# VLP.net
KiCad netlist of a schematic drawn in Altium Designer
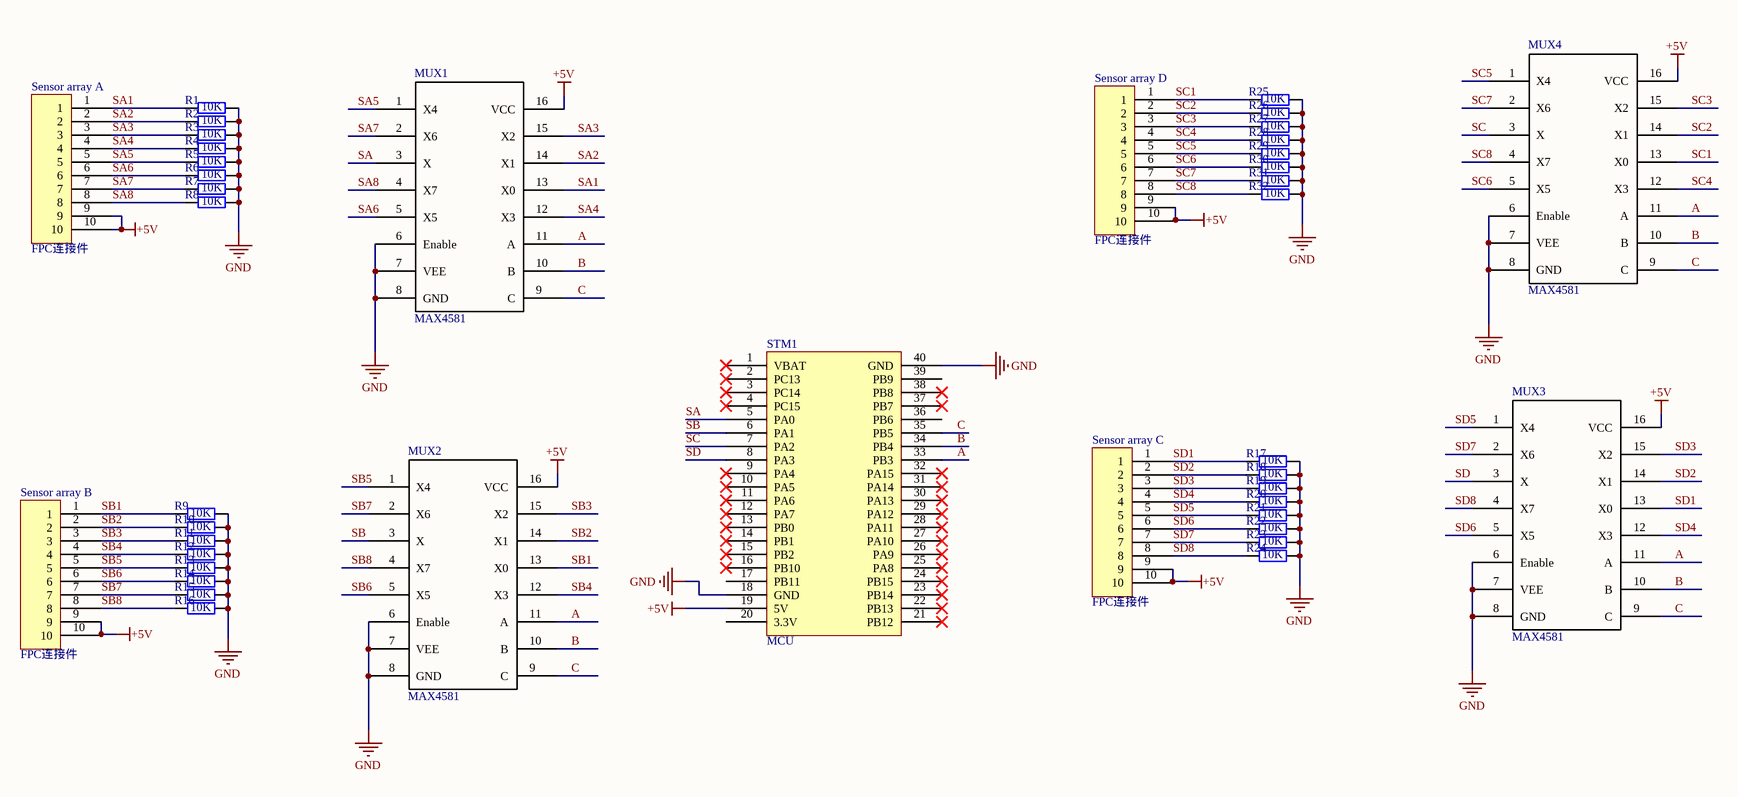
[diagram p0: VLP.SchDoc]

(export (version "E")
  (design (tool "Eeschema 10.0.6"))
  (components
    (comp (ref "MUX1") (value "MAX4581") (footprint "MAX4581") (libsource (lib "VLP") (part "MAX4581")))
    (comp (ref "MUX2") (value "MAX4581") (footprint "MAX4581") (libsource (lib "VLP") (part "MAX4581")))
    (comp (ref "MUX3") (value "MAX4581") (footprint "MAX4581") (libsource (lib "VLP") (part "MAX4581")))
    (comp (ref "MUX4") (value "MAX4581") (footprint "MAX4581") (libsource (lib "VLP") (part "MAX4581")))
    (comp (ref "R1")
      (value "10K")
      (footprint "0603c")
      (description "Resistor")
      (fields (field (name "Comment") "Res2") (field (name "PUBLISHER") "Altium Limited"))
      (libsource (lib "Miscellaneous Devices") (part "Res2"))
    )
    (comp (ref "R2")
      (value "10K")
      (footprint "0603c")
      (description "Resistor")
      (fields (field (name "Comment") "Res2") (field (name "PUBLISHER") "Altium Limited"))
      (libsource (lib "Miscellaneous Devices") (part "Res2"))
    )
    (comp (ref "R3")
      (value "10K")
      (footprint "0603c")
      (description "Resistor")
      (fields (field (name "Comment") "Res2") (field (name "PUBLISHER") "Altium Limited"))
      (libsource (lib "Miscellaneous Devices") (part "Res2"))
    )
    (comp (ref "R4")
      (value "10K")
      (footprint "0603c")
      (description "Resistor")
      (fields (field (name "Comment") "Res2") (field (name "PUBLISHER") "Altium Limited"))
      (libsource (lib "Miscellaneous Devices") (part "Res2"))
    )
    (comp (ref "R5")
      (value "10K")
      (footprint "0603c")
      (description "Resistor")
      (fields (field (name "Comment") "Res2") (field (name "PUBLISHER") "Altium Limited"))
      (libsource (lib "Miscellaneous Devices") (part "Res2"))
    )
    (comp (ref "R6")
      (value "10K")
      (footprint "0603c")
      (description "Resistor")
      (fields (field (name "Comment") "Res2") (field (name "PUBLISHER") "Altium Limited"))
      (libsource (lib "Miscellaneous Devices") (part "Res2"))
    )
    (comp (ref "R7")
      (value "10K")
      (footprint "0603c")
      (description "Resistor")
      (fields (field (name "Comment") "Res2") (field (name "PUBLISHER") "Altium Limited"))
      (libsource (lib "Miscellaneous Devices") (part "Res2"))
    )
    (comp (ref "R8")
      (value "10K")
      (footprint "0603c")
      (description "Resistor")
      (fields (field (name "Comment") "Res2") (field (name "PUBLISHER") "Altium Limited"))
      (libsource (lib "Miscellaneous Devices") (part "Res2"))
    )
    (comp (ref "R9")
      (value "10K")
      (footprint "0603c")
      (description "Resistor")
      (fields (field (name "Comment") "Res2") (field (name "PUBLISHER") "Altium Limited"))
      (libsource (lib "Miscellaneous Devices") (part "Res2"))
    )
    (comp (ref "R10")
      (value "10K")
      (footprint "0603c")
      (description "Resistor")
      (fields (field (name "Comment") "Res2") (field (name "PUBLISHER") "Altium Limited"))
      (libsource (lib "Miscellaneous Devices") (part "Res2"))
    )
    (comp (ref "R11")
      (value "10K")
      (footprint "0603c")
      (description "Resistor")
      (fields (field (name "Comment") "Res2") (field (name "PUBLISHER") "Altium Limited"))
      (libsource (lib "Miscellaneous Devices") (part "Res2"))
    )
    (comp (ref "R12")
      (value "10K")
      (footprint "0603c")
      (description "Resistor")
      (fields (field (name "Comment") "Res2") (field (name "PUBLISHER") "Altium Limited"))
      (libsource (lib "Miscellaneous Devices") (part "Res2"))
    )
    (comp (ref "R13")
      (value "10K")
      (footprint "0603c")
      (description "Resistor")
      (fields (field (name "Comment") "Res2") (field (name "PUBLISHER") "Altium Limited"))
      (libsource (lib "Miscellaneous Devices") (part "Res2"))
    )
    (comp (ref "R14")
      (value "10K")
      (footprint "0603c")
      (description "Resistor")
      (fields (field (name "Comment") "Res2") (field (name "PUBLISHER") "Altium Limited"))
      (libsource (lib "Miscellaneous Devices") (part "Res2"))
    )
    (comp (ref "R15")
      (value "10K")
      (footprint "0603c")
      (description "Resistor")
      (fields (field (name "Comment") "Res2") (field (name "PUBLISHER") "Altium Limited"))
      (libsource (lib "Miscellaneous Devices") (part "Res2"))
    )
    (comp (ref "R16")
      (value "10K")
      (footprint "0603c")
      (description "Resistor")
      (fields (field (name "Comment") "Res2") (field (name "PUBLISHER") "Altium Limited"))
      (libsource (lib "Miscellaneous Devices") (part "Res2"))
    )
    (comp (ref "R17")
      (value "10K")
      (footprint "0603c")
      (description "Resistor")
      (fields (field (name "Comment") "Res2") (field (name "PUBLISHER") "Altium Limited"))
      (libsource (lib "Miscellaneous Devices") (part "Res2"))
    )
    (comp (ref "R18")
      (value "10K")
      (footprint "0603c")
      (description "Resistor")
      (fields (field (name "Comment") "Res2") (field (name "PUBLISHER") "Altium Limited"))
      (libsource (lib "Miscellaneous Devices") (part "Res2"))
    )
    (comp (ref "R19")
      (value "10K")
      (footprint "0603c")
      (description "Resistor")
      (fields (field (name "Comment") "Res2") (field (name "PUBLISHER") "Altium Limited"))
      (libsource (lib "Miscellaneous Devices") (part "Res2"))
    )
    (comp (ref "R20")
      (value "10K")
      (footprint "0603c")
      (description "Resistor")
      (fields (field (name "Comment") "Res2") (field (name "PUBLISHER") "Altium Limited"))
      (libsource (lib "Miscellaneous Devices") (part "Res2"))
    )
    (comp (ref "R21")
      (value "10K")
      (footprint "0603c")
      (description "Resistor")
      (fields (field (name "Comment") "Res2") (field (name "PUBLISHER") "Altium Limited"))
      (libsource (lib "Miscellaneous Devices") (part "Res2"))
    )
    (comp (ref "R22")
      (value "10K")
      (footprint "0603c")
      (description "Resistor")
      (fields (field (name "Comment") "Res2") (field (name "PUBLISHER") "Altium Limited"))
      (libsource (lib "Miscellaneous Devices") (part "Res2"))
    )
    (comp (ref "R23")
      (value "10K")
      (footprint "0603c")
      (description "Resistor")
      (fields (field (name "Comment") "Res2") (field (name "PUBLISHER") "Altium Limited"))
      (libsource (lib "Miscellaneous Devices") (part "Res2"))
    )
    (comp (ref "R24")
      (value "10K")
      (footprint "0603c")
      (description "Resistor")
      (fields (field (name "Comment") "Res2") (field (name "PUBLISHER") "Altium Limited"))
      (libsource (lib "Miscellaneous Devices") (part "Res2"))
    )
    (comp (ref "R25")
      (value "10K")
      (footprint "0603c")
      (description "Resistor")
      (fields (field (name "Comment") "Res2") (field (name "PUBLISHER") "Altium Limited"))
      (libsource (lib "Miscellaneous Devices") (part "Res2"))
    )
    (comp (ref "R26")
      (value "10K")
      (footprint "0603c")
      (description "Resistor")
      (fields (field (name "Comment") "Res2") (field (name "PUBLISHER") "Altium Limited"))
      (libsource (lib "Miscellaneous Devices") (part "Res2"))
    )
    (comp (ref "R27")
      (value "10K")
      (footprint "0603c")
      (description "Resistor")
      (fields (field (name "Comment") "Res2") (field (name "PUBLISHER") "Altium Limited"))
      (libsource (lib "Miscellaneous Devices") (part "Res2"))
    )
    (comp (ref "R28")
      (value "10K")
      (footprint "0603c")
      (description "Resistor")
      (fields (field (name "Comment") "Res2") (field (name "PUBLISHER") "Altium Limited"))
      (libsource (lib "Miscellaneous Devices") (part "Res2"))
    )
    (comp (ref "R29")
      (value "10K")
      (footprint "0603c")
      (description "Resistor")
      (fields (field (name "Comment") "Res2") (field (name "PUBLISHER") "Altium Limited"))
      (libsource (lib "Miscellaneous Devices") (part "Res2"))
    )
    (comp (ref "R30")
      (value "10K")
      (footprint "0603c")
      (description "Resistor")
      (fields (field (name "Comment") "Res2") (field (name "PUBLISHER") "Altium Limited"))
      (libsource (lib "Miscellaneous Devices") (part "Res2"))
    )
    (comp (ref "R31")
      (value "10K")
      (footprint "0603c")
      (description "Resistor")
      (fields (field (name "Comment") "Res2") (field (name "PUBLISHER") "Altium Limited"))
      (libsource (lib "Miscellaneous Devices") (part "Res2"))
    )
    (comp (ref "R32")
      (value "10K")
      (footprint "0603c")
      (description "Resistor")
      (fields (field (name "Comment") "Res2") (field (name "PUBLISHER") "Altium Limited"))
      (libsource (lib "Miscellaneous Devices") (part "Res2"))
    )
    (comp (ref "Sensor array A")
      (value "FPC连接件")
      (footprint "FPC连接器-10P")
      (libsource (lib "altium-import") (part "root_0_FPC连接件_"))
    )
    (comp (ref "Sensor array B")
      (value "FPC连接件")
      (footprint "FPC连接器-10P")
      (libsource (lib "altium-import") (part "root_0_FPC连接件_"))
    )
    (comp (ref "Sensor array C")
      (value "FPC连接件")
      (footprint "FPC连接器-10P")
      (libsource (lib "altium-import") (part "root_0_FPC连接件_"))
    )
    (comp (ref "Sensor array D")
      (value "FPC连接件")
      (footprint "FPC连接器-10P")
      (libsource (lib "altium-import") (part "root_0_FPC连接件_"))
    )
    (comp (ref "STM1")
      (value "MCU")
      (footprint "STM32F103C8T6-4")
      (libsource (lib "STM32F103C8T6原理图库文件") (part "Component_1"))
    )
  )
  (nets
    (net (code "1") (name "+5V") (class "Default")
      (node (ref "MUX1") (pin "16") (pinfunction "VCC_16") (pintype "passive"))
      (node (ref "MUX2") (pin "16") (pinfunction "VCC_16") (pintype "passive"))
      (node (ref "MUX3") (pin "16") (pinfunction "VCC_16") (pintype "passive"))
      (node (ref "MUX4") (pin "16") (pinfunction "VCC_16") (pintype "passive"))
      (node (ref "STM1") (pin "19") (pinfunction "5V_19") (pintype "passive"))
      (node (ref "Sensor array A") (pin "10") (pinfunction "10_10") (pintype "passive"))
      (node (ref "Sensor array A") (pin "9") (pinfunction "9_9") (pintype "passive"))
      (node (ref "Sensor array B") (pin "10") (pinfunction "10_10") (pintype "passive"))
      (node (ref "Sensor array B") (pin "9") (pinfunction "9_9") (pintype "passive"))
      (node (ref "Sensor array C") (pin "10") (pinfunction "10_10") (pintype "passive"))
      (node (ref "Sensor array C") (pin "9") (pinfunction "9_9") (pintype "passive"))
      (node (ref "Sensor array D") (pin "10") (pinfunction "10_10") (pintype "passive"))
      (node (ref "Sensor array D") (pin "9") (pinfunction "9_9") (pintype "passive"))
    )
    (net (code "2") (name "/A") (class "Default")
      (node (ref "MUX1") (pin "11") (pinfunction "A_11") (pintype "passive"))
      (node (ref "MUX2") (pin "11") (pinfunction "A_11") (pintype "passive"))
      (node (ref "MUX3") (pin "11") (pinfunction "A_11") (pintype "passive"))
      (node (ref "MUX4") (pin "11") (pinfunction "A_11") (pintype "passive"))
      (node (ref "STM1") (pin "33") (pinfunction "PB3_33") (pintype "passive"))
    )
    (net (code "3") (name "/B") (class "Default")
      (node (ref "MUX1") (pin "10") (pinfunction "B_10") (pintype "passive"))
      (node (ref "MUX2") (pin "10") (pinfunction "B_10") (pintype "passive"))
      (node (ref "MUX3") (pin "10") (pinfunction "B_10") (pintype "passive"))
      (node (ref "MUX4") (pin "10") (pinfunction "B_10") (pintype "passive"))
      (node (ref "STM1") (pin "34") (pinfunction "PB4_34") (pintype "passive"))
    )
    (net (code "4") (name "/C") (class "Default")
      (node (ref "MUX1") (pin "9") (pinfunction "C_9") (pintype "passive"))
      (node (ref "MUX2") (pin "9") (pinfunction "C_9") (pintype "passive"))
      (node (ref "MUX3") (pin "9") (pinfunction "C_9") (pintype "passive"))
      (node (ref "MUX4") (pin "9") (pinfunction "C_9") (pintype "passive"))
      (node (ref "STM1") (pin "35") (pinfunction "PB5_35") (pintype "passive"))
    )
    (net (code "5") (name "/SA") (class "Default")
      (node (ref "MUX1") (pin "3") (pinfunction "X_3") (pintype "passive"))
      (node (ref "STM1") (pin "5") (pinfunction "PA0_5") (pintype "passive"))
    )
    (net (code "6") (name "/SA1") (class "Default")
      (node (ref "MUX1") (pin "13") (pinfunction "X0_13") (pintype "passive"))
      (node (ref "R1") (pin "1") (pinfunction "1_1") (pintype "passive"))
      (node (ref "Sensor array A") (pin "1") (pinfunction "1_1") (pintype "passive"))
    )
    (net (code "7") (name "/SA2") (class "Default")
      (node (ref "MUX1") (pin "14") (pinfunction "X1_14") (pintype "passive"))
      (node (ref "R2") (pin "1") (pinfunction "1_1") (pintype "passive"))
      (node (ref "Sensor array A") (pin "2") (pinfunction "2_2") (pintype "passive"))
    )
    (net (code "8") (name "/SA3") (class "Default")
      (node (ref "MUX1") (pin "15") (pinfunction "X2_15") (pintype "passive"))
      (node (ref "R3") (pin "1") (pinfunction "1_1") (pintype "passive"))
      (node (ref "Sensor array A") (pin "3") (pinfunction "3_3") (pintype "passive"))
    )
    (net (code "9") (name "/SA4") (class "Default")
      (node (ref "MUX1") (pin "12") (pinfunction "X3_12") (pintype "passive"))
      (node (ref "R4") (pin "1") (pinfunction "1_1") (pintype "passive"))
      (node (ref "Sensor array A") (pin "4") (pinfunction "4_4") (pintype "passive"))
    )
    (net (code "10") (name "/SA5") (class "Default")
      (node (ref "MUX1") (pin "1") (pinfunction "X4_1") (pintype "passive"))
      (node (ref "R5") (pin "1") (pinfunction "1_1") (pintype "passive"))
      (node (ref "Sensor array A") (pin "5") (pinfunction "5_5") (pintype "passive"))
    )
    (net (code "11") (name "/SA6") (class "Default")
      (node (ref "MUX1") (pin "5") (pinfunction "X5_5") (pintype "passive"))
      (node (ref "R6") (pin "1") (pinfunction "1_1") (pintype "passive"))
      (node (ref "Sensor array A") (pin "6") (pinfunction "6_6") (pintype "passive"))
    )
    (net (code "12") (name "/SA7") (class "Default")
      (node (ref "MUX1") (pin "2") (pinfunction "X6_2") (pintype "passive"))
      (node (ref "R7") (pin "1") (pinfunction "1_1") (pintype "passive"))
      (node (ref "Sensor array A") (pin "7") (pinfunction "7_7") (pintype "passive"))
    )
    (net (code "13") (name "/SA8") (class "Default")
      (node (ref "MUX1") (pin "4") (pinfunction "X7_4") (pintype "passive"))
      (node (ref "R8") (pin "1") (pinfunction "1_1") (pintype "passive"))
      (node (ref "Sensor array A") (pin "8") (pinfunction "8_8") (pintype "passive"))
    )
    (net (code "14") (name "/SB") (class "Default")
      (node (ref "MUX2") (pin "3") (pinfunction "X_3") (pintype "passive"))
      (node (ref "STM1") (pin "6") (pinfunction "PA1_6") (pintype "passive"))
    )
    (net (code "15") (name "/SB1") (class "Default")
      (node (ref "MUX2") (pin "13") (pinfunction "X0_13") (pintype "passive"))
      (node (ref "R9") (pin "1") (pinfunction "1_1") (pintype "passive"))
      (node (ref "Sensor array B") (pin "1") (pinfunction "1_1") (pintype "passive"))
    )
    (net (code "16") (name "/SB2") (class "Default")
      (node (ref "MUX2") (pin "14") (pinfunction "X1_14") (pintype "passive"))
      (node (ref "R10") (pin "1") (pinfunction "1_1") (pintype "passive"))
      (node (ref "Sensor array B") (pin "2") (pinfunction "2_2") (pintype "passive"))
    )
    (net (code "17") (name "/SB3") (class "Default")
      (node (ref "MUX2") (pin "15") (pinfunction "X2_15") (pintype "passive"))
      (node (ref "R11") (pin "1") (pinfunction "1_1") (pintype "passive"))
      (node (ref "Sensor array B") (pin "3") (pinfunction "3_3") (pintype "passive"))
    )
    (net (code "18") (name "/SB4") (class "Default")
      (node (ref "MUX2") (pin "12") (pinfunction "X3_12") (pintype "passive"))
      (node (ref "R12") (pin "1") (pinfunction "1_1") (pintype "passive"))
      (node (ref "Sensor array B") (pin "4") (pinfunction "4_4") (pintype "passive"))
    )
    (net (code "19") (name "/SB5") (class "Default")
      (node (ref "MUX2") (pin "1") (pinfunction "X4_1") (pintype "passive"))
      (node (ref "R13") (pin "1") (pinfunction "1_1") (pintype "passive"))
      (node (ref "Sensor array B") (pin "5") (pinfunction "5_5") (pintype "passive"))
    )
    (net (code "20") (name "/SB6") (class "Default")
      (node (ref "MUX2") (pin "5") (pinfunction "X5_5") (pintype "passive"))
      (node (ref "R14") (pin "1") (pinfunction "1_1") (pintype "passive"))
      (node (ref "Sensor array B") (pin "6") (pinfunction "6_6") (pintype "passive"))
    )
    (net (code "21") (name "/SB7") (class "Default")
      (node (ref "MUX2") (pin "2") (pinfunction "X6_2") (pintype "passive"))
      (node (ref "R15") (pin "1") (pinfunction "1_1") (pintype "passive"))
      (node (ref "Sensor array B") (pin "7") (pinfunction "7_7") (pintype "passive"))
    )
    (net (code "22") (name "/SB8") (class "Default")
      (node (ref "MUX2") (pin "4") (pinfunction "X7_4") (pintype "passive"))
      (node (ref "R16") (pin "1") (pinfunction "1_1") (pintype "passive"))
      (node (ref "Sensor array B") (pin "8") (pinfunction "8_8") (pintype "passive"))
    )
    (net (code "23") (name "/SC") (class "Default")
      (node (ref "MUX4") (pin "3") (pinfunction "X_3") (pintype "passive"))
      (node (ref "STM1") (pin "7") (pinfunction "PA2_7") (pintype "passive"))
    )
    (net (code "24") (name "/SC1") (class "Default")
      (node (ref "MUX4") (pin "13") (pinfunction "X0_13") (pintype "passive"))
      (node (ref "R25") (pin "1") (pinfunction "1_1") (pintype "passive"))
      (node (ref "Sensor array D") (pin "1") (pinfunction "1_1") (pintype "passive"))
    )
    (net (code "25") (name "/SC2") (class "Default")
      (node (ref "MUX4") (pin "14") (pinfunction "X1_14") (pintype "passive"))
      (node (ref "R26") (pin "1") (pinfunction "1_1") (pintype "passive"))
      (node (ref "Sensor array D") (pin "2") (pinfunction "2_2") (pintype "passive"))
    )
    (net (code "26") (name "/SC3") (class "Default")
      (node (ref "MUX4") (pin "15") (pinfunction "X2_15") (pintype "passive"))
      (node (ref "R27") (pin "1") (pinfunction "1_1") (pintype "passive"))
      (node (ref "Sensor array D") (pin "3") (pinfunction "3_3") (pintype "passive"))
    )
    (net (code "27") (name "/SC4") (class "Default")
      (node (ref "MUX4") (pin "12") (pinfunction "X3_12") (pintype "passive"))
      (node (ref "R28") (pin "1") (pinfunction "1_1") (pintype "passive"))
      (node (ref "Sensor array D") (pin "4") (pinfunction "4_4") (pintype "passive"))
    )
    (net (code "28") (name "/SC5") (class "Default")
      (node (ref "MUX4") (pin "1") (pinfunction "X4_1") (pintype "passive"))
      (node (ref "R29") (pin "1") (pinfunction "1_1") (pintype "passive"))
      (node (ref "Sensor array D") (pin "5") (pinfunction "5_5") (pintype "passive"))
    )
    (net (code "29") (name "/SC6") (class "Default")
      (node (ref "MUX4") (pin "5") (pinfunction "X5_5") (pintype "passive"))
      (node (ref "R30") (pin "1") (pinfunction "1_1") (pintype "passive"))
      (node (ref "Sensor array D") (pin "6") (pinfunction "6_6") (pintype "passive"))
    )
    (net (code "30") (name "/SC7") (class "Default")
      (node (ref "MUX4") (pin "2") (pinfunction "X6_2") (pintype "passive"))
      (node (ref "R31") (pin "1") (pinfunction "1_1") (pintype "passive"))
      (node (ref "Sensor array D") (pin "7") (pinfunction "7_7") (pintype "passive"))
    )
    (net (code "31") (name "/SC8") (class "Default")
      (node (ref "MUX4") (pin "4") (pinfunction "X7_4") (pintype "passive"))
      (node (ref "R32") (pin "1") (pinfunction "1_1") (pintype "passive"))
      (node (ref "Sensor array D") (pin "8") (pinfunction "8_8") (pintype "passive"))
    )
    (net (code "32") (name "/SD") (class "Default")
      (node (ref "MUX3") (pin "3") (pinfunction "X_3") (pintype "passive"))
      (node (ref "STM1") (pin "8") (pinfunction "PA3_8") (pintype "passive"))
    )
    (net (code "33") (name "/SD1") (class "Default")
      (node (ref "MUX3") (pin "13") (pinfunction "X0_13") (pintype "passive"))
      (node (ref "R17") (pin "1") (pinfunction "1_1") (pintype "passive"))
      (node (ref "Sensor array C") (pin "1") (pinfunction "1_1") (pintype "passive"))
    )
    (net (code "34") (name "/SD2") (class "Default")
      (node (ref "MUX3") (pin "14") (pinfunction "X1_14") (pintype "passive"))
      (node (ref "R18") (pin "1") (pinfunction "1_1") (pintype "passive"))
      (node (ref "Sensor array C") (pin "2") (pinfunction "2_2") (pintype "passive"))
    )
    (net (code "35") (name "/SD3") (class "Default")
      (node (ref "MUX3") (pin "15") (pinfunction "X2_15") (pintype "passive"))
      (node (ref "R19") (pin "1") (pinfunction "1_1") (pintype "passive"))
      (node (ref "Sensor array C") (pin "3") (pinfunction "3_3") (pintype "passive"))
    )
    (net (code "36") (name "/SD4") (class "Default")
      (node (ref "MUX3") (pin "12") (pinfunction "X3_12") (pintype "passive"))
      (node (ref "R20") (pin "1") (pinfunction "1_1") (pintype "passive"))
      (node (ref "Sensor array C") (pin "4") (pinfunction "4_4") (pintype "passive"))
    )
    (net (code "37") (name "/SD5") (class "Default")
      (node (ref "MUX3") (pin "1") (pinfunction "X4_1") (pintype "passive"))
      (node (ref "R21") (pin "1") (pinfunction "1_1") (pintype "passive"))
      (node (ref "Sensor array C") (pin "5") (pinfunction "5_5") (pintype "passive"))
    )
    (net (code "38") (name "/SD6") (class "Default")
      (node (ref "MUX3") (pin "5") (pinfunction "X5_5") (pintype "passive"))
      (node (ref "R22") (pin "1") (pinfunction "1_1") (pintype "passive"))
      (node (ref "Sensor array C") (pin "6") (pinfunction "6_6") (pintype "passive"))
    )
    (net (code "39") (name "/SD7") (class "Default")
      (node (ref "MUX3") (pin "2") (pinfunction "X6_2") (pintype "passive"))
      (node (ref "R23") (pin "1") (pinfunction "1_1") (pintype "passive"))
      (node (ref "Sensor array C") (pin "7") (pinfunction "7_7") (pintype "passive"))
    )
    (net (code "40") (name "/SD8") (class "Default")
      (node (ref "MUX3") (pin "4") (pinfunction "X7_4") (pintype "passive"))
      (node (ref "R24") (pin "1") (pinfunction "1_1") (pintype "passive"))
      (node (ref "Sensor array C") (pin "8") (pinfunction "8_8") (pintype "passive"))
    )
    (net (code "41") (name "GND") (class "Default")
      (node (ref "MUX1") (pin "6") (pinfunction "Enable_6") (pintype "passive"))
      (node (ref "MUX1") (pin "7") (pinfunction "VEE_7") (pintype "passive"))
      (node (ref "MUX1") (pin "8") (pinfunction "GND_8") (pintype "passive"))
      (node (ref "MUX2") (pin "6") (pinfunction "Enable_6") (pintype "passive"))
      (node (ref "MUX2") (pin "7") (pinfunction "VEE_7") (pintype "passive"))
      (node (ref "MUX2") (pin "8") (pinfunction "GND_8") (pintype "passive"))
      (node (ref "MUX3") (pin "6") (pinfunction "Enable_6") (pintype "passive"))
      (node (ref "MUX3") (pin "7") (pinfunction "VEE_7") (pintype "passive"))
      (node (ref "MUX3") (pin "8") (pinfunction "GND_8") (pintype "passive"))
      (node (ref "MUX4") (pin "6") (pinfunction "Enable_6") (pintype "passive"))
      (node (ref "MUX4") (pin "7") (pinfunction "VEE_7") (pintype "passive"))
      (node (ref "MUX4") (pin "8") (pinfunction "GND_8") (pintype "passive"))
      (node (ref "R1") (pin "2") (pinfunction "2_2") (pintype "passive"))
      (node (ref "R10") (pin "2") (pinfunction "2_2") (pintype "passive"))
      (node (ref "R11") (pin "2") (pinfunction "2_2") (pintype "passive"))
      (node (ref "R12") (pin "2") (pinfunction "2_2") (pintype "passive"))
      (node (ref "R13") (pin "2") (pinfunction "2_2") (pintype "passive"))
      (node (ref "R14") (pin "2") (pinfunction "2_2") (pintype "passive"))
      (node (ref "R15") (pin "2") (pinfunction "2_2") (pintype "passive"))
      (node (ref "R16") (pin "2") (pinfunction "2_2") (pintype "passive"))
      (node (ref "R17") (pin "2") (pinfunction "2_2") (pintype "passive"))
      (node (ref "R18") (pin "2") (pinfunction "2_2") (pintype "passive"))
      (node (ref "R19") (pin "2") (pinfunction "2_2") (pintype "passive"))
      (node (ref "R2") (pin "2") (pinfunction "2_2") (pintype "passive"))
      (node (ref "R20") (pin "2") (pinfunction "2_2") (pintype "passive"))
      (node (ref "R21") (pin "2") (pinfunction "2_2") (pintype "passive"))
      (node (ref "R22") (pin "2") (pinfunction "2_2") (pintype "passive"))
      (node (ref "R23") (pin "2") (pinfunction "2_2") (pintype "passive"))
      (node (ref "R24") (pin "2") (pinfunction "2_2") (pintype "passive"))
      (node (ref "R25") (pin "2") (pinfunction "2_2") (pintype "passive"))
      (node (ref "R26") (pin "2") (pinfunction "2_2") (pintype "passive"))
      (node (ref "R27") (pin "2") (pinfunction "2_2") (pintype "passive"))
      (node (ref "R28") (pin "2") (pinfunction "2_2") (pintype "passive"))
      (node (ref "R29") (pin "2") (pinfunction "2_2") (pintype "passive"))
      (node (ref "R3") (pin "2") (pinfunction "2_2") (pintype "passive"))
      (node (ref "R30") (pin "2") (pinfunction "2_2") (pintype "passive"))
      (node (ref "R31") (pin "2") (pinfunction "2_2") (pintype "passive"))
      (node (ref "R32") (pin "2") (pinfunction "2_2") (pintype "passive"))
      (node (ref "R4") (pin "2") (pinfunction "2_2") (pintype "passive"))
      (node (ref "R5") (pin "2") (pinfunction "2_2") (pintype "passive"))
      (node (ref "R6") (pin "2") (pinfunction "2_2") (pintype "passive"))
      (node (ref "R7") (pin "2") (pinfunction "2_2") (pintype "passive"))
      (node (ref "R8") (pin "2") (pinfunction "2_2") (pintype "passive"))
      (node (ref "R9") (pin "2") (pinfunction "2_2") (pintype "passive"))
      (node (ref "STM1") (pin "18") (pinfunction "GND_18") (pintype "passive"))
      (node (ref "STM1") (pin "40") (pinfunction "GND_40") (pintype "passive"))
    )
    (net (code "42") (name "unconnected-(STM1-3.3V-Pad20)") (class "Default")
      (node (ref "STM1") (pin "20") (pinfunction "3.3V_20") (pintype "passive"))
    )
    (net (code "43") (name "unconnected-(STM1-PA4-Pad9)") (class "Default")
      (node (ref "STM1") (pin "9") (pinfunction "PA4_9") (pintype "passive+no_connect"))
    )
    (net (code "44") (name "unconnected-(STM1-PA5-Pad10)") (class "Default")
      (node (ref "STM1") (pin "10") (pinfunction "PA5_10") (pintype "passive+no_connect"))
    )
    (net (code "45") (name "unconnected-(STM1-PA6-Pad11)") (class "Default")
      (node (ref "STM1") (pin "11") (pinfunction "PA6_11") (pintype "passive+no_connect"))
    )
    (net (code "46") (name "unconnected-(STM1-PA7-Pad12)") (class "Default")
      (node (ref "STM1") (pin "12") (pinfunction "PA7_12") (pintype "passive+no_connect"))
    )
    (net (code "47") (name "unconnected-(STM1-PA8-Pad25)") (class "Default")
      (node (ref "STM1") (pin "25") (pinfunction "PA8_25") (pintype "passive+no_connect"))
    )
    (net (code "48") (name "unconnected-(STM1-PA9-Pad26)") (class "Default")
      (node (ref "STM1") (pin "26") (pinfunction "PA9_26") (pintype "passive+no_connect"))
    )
    (net (code "49") (name "unconnected-(STM1-PA10-Pad27)") (class "Default")
      (node (ref "STM1") (pin "27") (pinfunction "PA10_27") (pintype "passive+no_connect"))
    )
    (net (code "50") (name "unconnected-(STM1-PA11-Pad28)") (class "Default")
      (node (ref "STM1") (pin "28") (pinfunction "PA11_28") (pintype "passive+no_connect"))
    )
    (net (code "51") (name "unconnected-(STM1-PA12-Pad29)") (class "Default")
      (node (ref "STM1") (pin "29") (pinfunction "PA12_29") (pintype "passive+no_connect"))
    )
    (net (code "52") (name "unconnected-(STM1-PA13-Pad30)") (class "Default")
      (node (ref "STM1") (pin "30") (pinfunction "PA13_30") (pintype "passive+no_connect"))
    )
    (net (code "53") (name "unconnected-(STM1-PA14-Pad31)") (class "Default")
      (node (ref "STM1") (pin "31") (pinfunction "PA14_31") (pintype "passive+no_connect"))
    )
    (net (code "54") (name "unconnected-(STM1-PA15-Pad32)") (class "Default")
      (node (ref "STM1") (pin "32") (pinfunction "PA15_32") (pintype "passive+no_connect"))
    )
    (net (code "55") (name "unconnected-(STM1-PB0-Pad13)") (class "Default")
      (node (ref "STM1") (pin "13") (pinfunction "PB0_13") (pintype "passive+no_connect"))
    )
    (net (code "56") (name "unconnected-(STM1-PB1-Pad14)") (class "Default")
      (node (ref "STM1") (pin "14") (pinfunction "PB1_14") (pintype "passive+no_connect"))
    )
    (net (code "57") (name "unconnected-(STM1-PB2-Pad15)") (class "Default")
      (node (ref "STM1") (pin "15") (pinfunction "PB2_15") (pintype "passive+no_connect"))
    )
    (net (code "58") (name "unconnected-(STM1-PB6-Pad36)") (class "Default")
      (node (ref "STM1") (pin "36") (pinfunction "PB6_36") (pintype "passive"))
    )
    (net (code "59") (name "unconnected-(STM1-PB7-Pad37)") (class "Default")
      (node (ref "STM1") (pin "37") (pinfunction "PB7_37") (pintype "passive+no_connect"))
    )
    (net (code "60") (name "unconnected-(STM1-PB8-Pad38)") (class "Default")
      (node (ref "STM1") (pin "38") (pinfunction "PB8_38") (pintype "passive+no_connect"))
    )
    (net (code "61") (name "unconnected-(STM1-PB9-Pad39)") (class "Default")
      (node (ref "STM1") (pin "39") (pinfunction "PB9_39") (pintype "passive"))
    )
    (net (code "62") (name "unconnected-(STM1-PB10-Pad16)") (class "Default")
      (node (ref "STM1") (pin "16") (pinfunction "PB10_16") (pintype "passive+no_connect"))
    )
    (net (code "63") (name "unconnected-(STM1-PB11-Pad17)") (class "Default")
      (node (ref "STM1") (pin "17") (pinfunction "PB11_17") (pintype "passive"))
    )
    (net (code "64") (name "unconnected-(STM1-PB12-Pad21)") (class "Default")
      (node (ref "STM1") (pin "21") (pinfunction "PB12_21") (pintype "passive+no_connect"))
    )
    (net (code "65") (name "unconnected-(STM1-PB13-Pad22)") (class "Default")
      (node (ref "STM1") (pin "22") (pinfunction "PB13_22") (pintype "passive+no_connect"))
    )
    (net (code "66") (name "unconnected-(STM1-PB14-Pad23)") (class "Default")
      (node (ref "STM1") (pin "23") (pinfunction "PB14_23") (pintype "passive+no_connect"))
    )
    (net (code "67") (name "unconnected-(STM1-PB15-Pad24)") (class "Default")
      (node (ref "STM1") (pin "24") (pinfunction "PB15_24") (pintype "passive+no_connect"))
    )
    (net (code "68") (name "unconnected-(STM1-PC13-Pad2)") (class "Default")
      (node (ref "STM1") (pin "2") (pinfunction "PC13_2") (pintype "passive+no_connect"))
    )
    (net (code "69") (name "unconnected-(STM1-PC14-Pad3)") (class "Default")
      (node (ref "STM1") (pin "3") (pinfunction "PC14_3") (pintype "passive+no_connect"))
    )
    (net (code "70") (name "unconnected-(STM1-PC15-Pad4)") (class "Default")
      (node (ref "STM1") (pin "4") (pinfunction "PC15_4") (pintype "passive+no_connect"))
    )
    (net (code "71") (name "unconnected-(STM1-VBAT-Pad1)") (class "Default")
      (node (ref "STM1") (pin "1") (pinfunction "VBAT_1") (pintype "passive+no_connect"))
    )
  )
)
